# wifi_switch.net
KiCad netlist of a schematic drawn in EAGLE
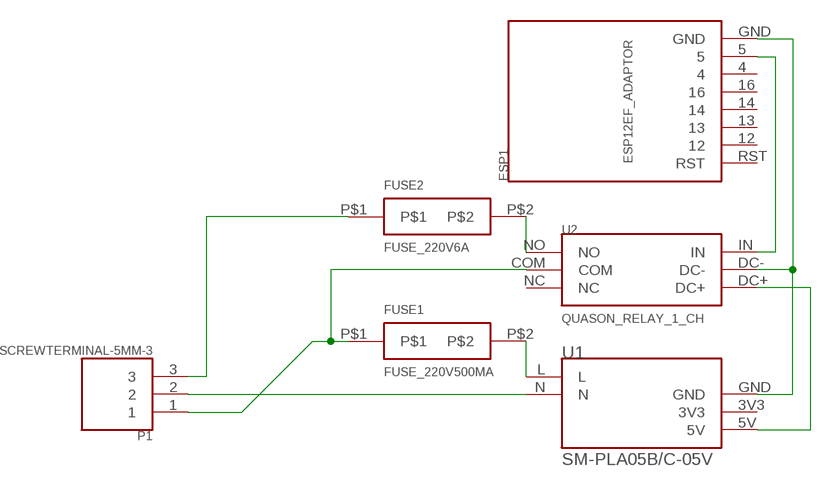
[diagram p0: schematic, sheet 1]

(export (version "E")
  (design (tool "Eeschema 10.0.6"))
  (components
    (comp (ref "ESP1")
      (value "ESP12EF_ADAPTOR")
      (footprint "eagle-import:ESP12EF_ADAPTOR")
      (libsource (lib "eagle-import") (part "ESP12EF_ADAPTOR"))
    )
    (comp (ref "FUSE1")
      (value "FUSE_220V500MA")
      (footprint "eagle-import:FUSE_220V_5X20MM")
      (libsource (lib "eagle-import") (part "FUSE_220V500MA"))
    )
    (comp (ref "FUSE2")
      (value "FUSE_220V6A")
      (footprint "eagle-import:FUSE_220V_5X20MM")
      (libsource (lib "eagle-import") (part "FUSE_220V6A"))
    )
    (comp (ref "P1")
      (value "SCREWTERMINAL-5MM-3")
      (footprint "eagle-import:SCREWTERMINAL-5MM-3")
      (libsource (lib "eagle-import") (part "SCREWTERMINAL-5MM-3"))
    )
    (comp (ref "U1")
      (value "SM-PLA05B/C-05V")
      (footprint "eagle-import:SM-PLA05B_C-05V")
      (libsource (lib "eagle-import") (part "SM-PLA05B/C-05V"))
    )
    (comp (ref "U2")
      (value "QUASON_RELAY_1_CH")
      (footprint "eagle-import:QUASON_RELAY_1_CH")
      (libsource (lib "eagle-import") (part "QUASON_RELAY_1_CH"))
    )
  )
  (nets
    (net (code "1") (name "Net-(ESP1-Pad5)") (class "Default")
      (node (ref "ESP1") (pin "5") (pinfunction "5_5") (pintype "bidirectional"))
      (node (ref "U2") (pin "IN") (pinfunction "IN_IN") (pintype "bidirectional"))
    )
    (net (code "2") (name "Net-(ESP1-PadGND)") (class "Default")
      (node (ref "ESP1") (pin "GND") (pinfunction "GND_GND") (pintype "bidirectional"))
      (node (ref "U1") (pin "GND") (pinfunction "GND_GND") (pintype "bidirectional"))
      (node (ref "U2") (pin "DC-") (pinfunction "DC-_DC-") (pintype "bidirectional"))
    )
    (net (code "3") (name "Net-(FUSE1-PadP$1)") (class "Default")
      (node (ref "FUSE1") (pin "P$1") (pinfunction "P$1_P$1") (pintype "bidirectional"))
      (node (ref "P1") (pin "1") (pinfunction "1_1") (pintype "passive"))
      (node (ref "U2") (pin "COM") (pinfunction "COM_COM") (pintype "bidirectional"))
    )
    (net (code "4") (name "Net-(FUSE1-PadP$2)") (class "Default")
      (node (ref "FUSE1") (pin "P$2") (pinfunction "P$2_P$2") (pintype "bidirectional"))
      (node (ref "U1") (pin "L") (pinfunction "L_L") (pintype "bidirectional"))
    )
    (net (code "5") (name "Net-(FUSE2-PadP$1)") (class "Default")
      (node (ref "FUSE2") (pin "P$1") (pinfunction "P$1_P$1") (pintype "bidirectional"))
      (node (ref "P1") (pin "3") (pinfunction "3_3") (pintype "passive"))
    )
    (net (code "6") (name "Net-(FUSE2-PadP$2)") (class "Default")
      (node (ref "FUSE2") (pin "P$2") (pinfunction "P$2_P$2") (pintype "bidirectional"))
      (node (ref "U2") (pin "NO") (pinfunction "NO_NO") (pintype "bidirectional"))
    )
    (net (code "7") (name "Net-(P1-Pad2)") (class "Default")
      (node (ref "P1") (pin "2") (pinfunction "2_2") (pintype "passive"))
      (node (ref "U1") (pin "N") (pinfunction "N_N") (pintype "bidirectional"))
    )
    (net (code "8") (name "Net-(U1-Pad5V)") (class "Default")
      (node (ref "U1") (pin "5V") (pinfunction "5V_5V") (pintype "bidirectional"))
      (node (ref "U2") (pin "DC+") (pinfunction "DC+_DC+") (pintype "bidirectional"))
    )
    (net (code "9") (name "unconnected-(ESP1-Pad4)") (class "Default")
      (node (ref "ESP1") (pin "4") (pinfunction "4_4") (pintype "bidirectional"))
    )
    (net (code "10") (name "unconnected-(ESP1-Pad12)") (class "Default")
      (node (ref "ESP1") (pin "12") (pinfunction "12_12") (pintype "bidirectional"))
    )
    (net (code "11") (name "unconnected-(ESP1-Pad13)") (class "Default")
      (node (ref "ESP1") (pin "13") (pinfunction "13_13") (pintype "bidirectional"))
    )
    (net (code "12") (name "unconnected-(ESP1-Pad14)") (class "Default")
      (node (ref "ESP1") (pin "14") (pinfunction "14_14") (pintype "bidirectional"))
    )
    (net (code "13") (name "unconnected-(ESP1-Pad16)") (class "Default")
      (node (ref "ESP1") (pin "16") (pinfunction "16_16") (pintype "bidirectional"))
    )
    (net (code "14") (name "unconnected-(ESP1-PadRST)") (class "Default")
      (node (ref "ESP1") (pin "RST") (pinfunction "RST_RST") (pintype "bidirectional"))
    )
    (net (code "15") (name "unconnected-(U1-Pad3V3)") (class "Default")
      (node (ref "U1") (pin "3V3") (pinfunction "3V3_3V3") (pintype "bidirectional"))
    )
    (net (code "16") (name "unconnected-(U2-PadNC)") (class "Default")
      (node (ref "U2") (pin "NC") (pinfunction "NC_NC") (pintype "bidirectional"))
    )
  )
)
